# Sheet3.net
KiCad netlist of a schematic drawn in Altium Designer
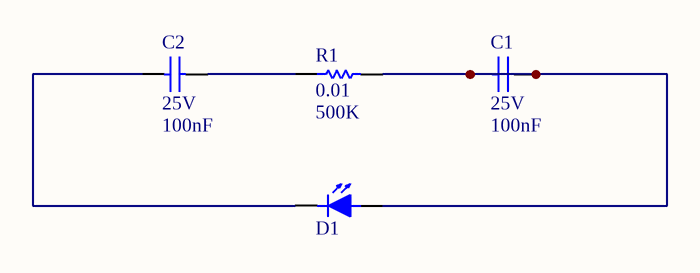
[diagram p0: Sheet3.SchDoc]

(export (version "E")
  (design (tool "Eeschema 10.0.6"))
  (components
    (comp (ref "C1")
      (value "100nF")
      (footprint "Cap 0603 (1608 Metric)")
      (description "0603 (1608 Metric) 4-200V SMD Capacitor")
      (fields
        (field (name "MANUFACTURER") "Various")
        (field (name "VOLTAGE RATING") "25V")
        (field (name "Comment") "Cap 0603 (1608 Metric)")
      )
      (libsource (lib "Database_Libs2(for report)") (part "Cap 0603 (1608 Metric)"))
    )
    (comp (ref "C2")
      (value "100nF")
      (footprint "Cap 0603 (1608 Metric)")
      (description "0603 (1608 Metric) 4-200V SMD Capacitor")
      (fields
        (field (name "MANUFACTURER") "Various")
        (field (name "VOLTAGE RATING") "25V")
        (field (name "Comment") "Cap 0603 (1608 Metric)")
      )
      (libsource (lib "Database_Libs2(for report)") (part "Cap 0603 (1608 Metric)"))
    )
    (comp (ref "D1")
      (value "0805 (2.0mmx1.25mm)")
      (footprint "D0805")
      (description "KP-2012, KPT-2012, KPHCM-2012 Series")
      (fields
        (field (name "MANUFACTURER") "Kingbright")
        (field (name "MANUFACTURER PART NUMBER") "KP-2012QBC-D")
      )
      (libsource (lib "Database_Libs2(for report)") (part "0805 (2.0mmx1.25mm)"))
    )
    (comp (ref "R1")
      (value "500K")
      (footprint "Res 0603 (1608 Metric)")
      (description "0603 (1608 Metric) 0.1W SMD Resistor")
      (fields
        (field (name "MANUFACTURER PART NUMBER") "Various")
        (field (name "TOLERANCE") "0.01")
        (field (name "Comment") "Res 0603 (1608 Metric)")
      )
      (libsource (lib "Database_Libs2(for report)") (part "Res 0603 (1608 Metric)"))
    )
  )
  (nets
    (net (code "1") (name "Net-(C1-Pad1)") (class "Default")
      (node (ref "C1") (pin "1") (pinfunction "1_1") (pintype "passive"))
      (node (ref "C1") (pin "2") (pinfunction "2_2") (pintype "passive"))
      (node (ref "D1") (pin "A") (pinfunction "A_A") (pintype "passive"))
      (node (ref "R1") (pin "2") (pinfunction "2_2") (pintype "passive"))
    )
    (net (code "2") (name "Net-(C2-Pad1)") (class "Default")
      (node (ref "C2") (pin "1") (pinfunction "1_1") (pintype "passive"))
      (node (ref "D1") (pin "C") (pinfunction "C_C") (pintype "passive"))
    )
    (net (code "3") (name "Net-(C2-Pad2)") (class "Default")
      (node (ref "C2") (pin "2") (pinfunction "2_2") (pintype "passive"))
      (node (ref "R1") (pin "1") (pinfunction "1_1") (pintype "passive"))
    )
  )
)
